# Breakout_v2.net
KiCad netlist of a schematic drawn in EAGLE
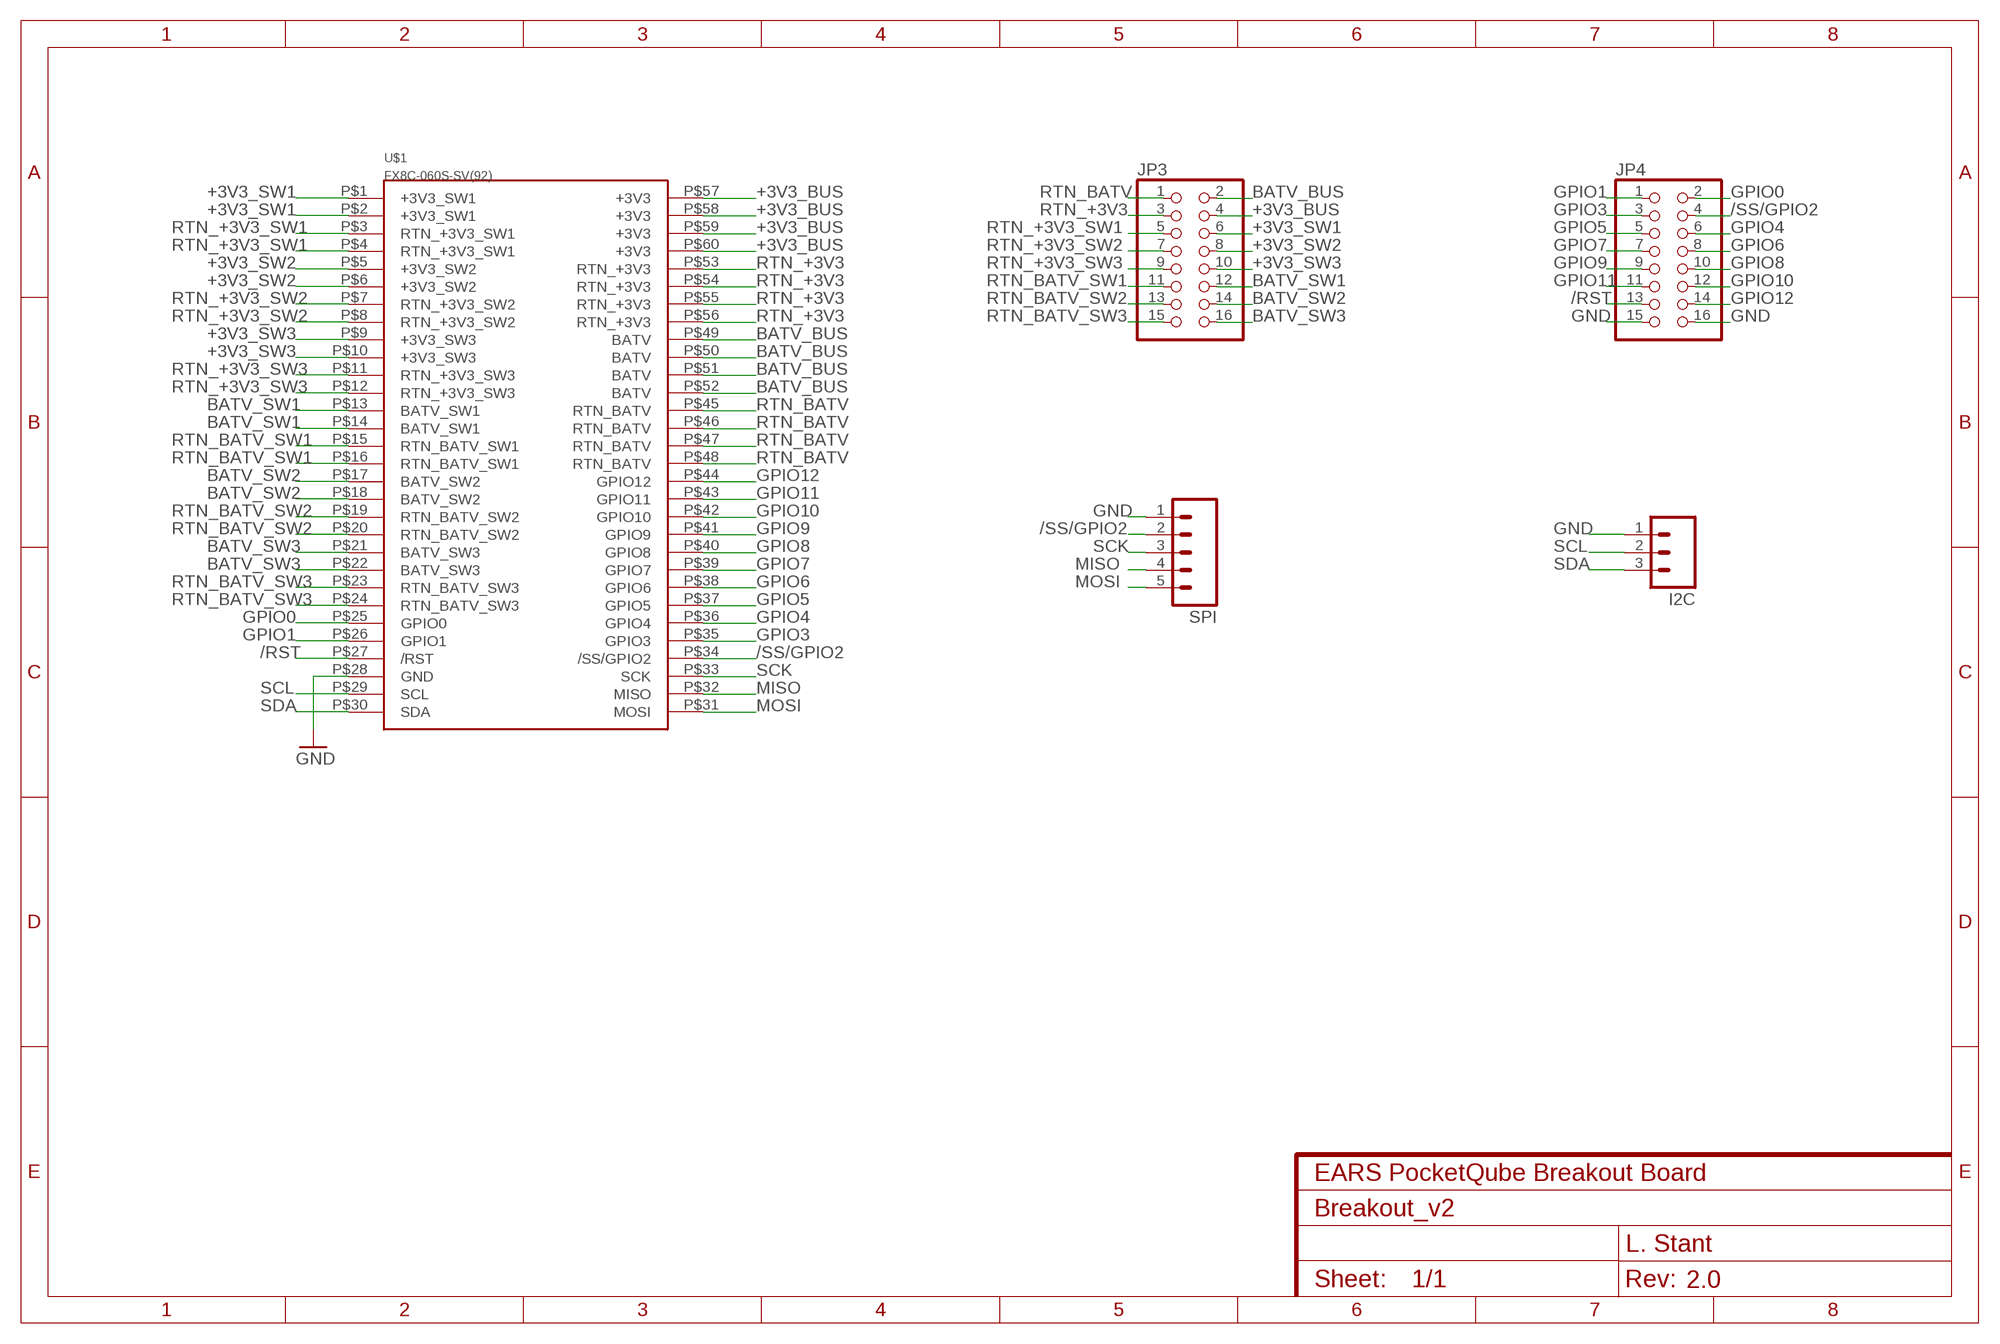
[diagram p0: schematic, sheet 1]

(export (version "E")
  (design (tool "Eeschema 10.0.6"))
  (components
    (comp (ref "I2C")
      (value "M03PTH")
      (footprint "eagle-import:1X03")
      (libsource (lib "eagle-import") (part "M03PTH"))
    )
    (comp (ref "JP3")
      (value "PINHD-2X8")
      (footprint "eagle-import:2X08")
      (libsource (lib "eagle-import") (part "PINHD-2X8"))
    )
    (comp (ref "JP4")
      (value "PINHD-2X8")
      (footprint "eagle-import:2X08")
      (libsource (lib "eagle-import") (part "PINHD-2X8"))
    )
    (comp (ref "SPI")
      (value "M05PTH")
      (footprint "eagle-import:1X05")
      (libsource (lib "eagle-import") (part "M05PTH"))
    )
    (comp (ref "U$1")
      (value "FX8C-060S-SV(92)")
      (footprint "eagle-import:FX8C-060S-SV(92)")
      (libsource (lib "eagle-import") (part "FX8C-060S-SV(92)"))
    )
  )
  (nets
    (net (code "1") (name "/+3V3_BUS") (class "Default")
      (node (ref "JP3") (pin "4") (pinfunction "4_4") (pintype "passive"))
      (node (ref "U$1") (pin "P$57") (pinfunction "+3V3_P$57") (pintype "power_in"))
      (node (ref "U$1") (pin "P$58") (pinfunction "+3V3_P$58") (pintype "power_in"))
      (node (ref "U$1") (pin "P$59") (pinfunction "+3V3_P$59") (pintype "power_in"))
      (node (ref "U$1") (pin "P$60") (pinfunction "+3V3_P$60") (pintype "power_in"))
    )
    (net (code "2") (name "/+3V3_SW1") (class "Default")
      (node (ref "JP3") (pin "6") (pinfunction "6_6") (pintype "passive"))
      (node (ref "U$1") (pin "P$1") (pinfunction "+3V3_SW1_P$1") (pintype "power_in"))
      (node (ref "U$1") (pin "P$2") (pinfunction "+3V3_SW1_P$2") (pintype "power_in"))
    )
    (net (code "3") (name "/+3V3_SW2") (class "Default")
      (node (ref "JP3") (pin "8") (pinfunction "8_8") (pintype "passive"))
      (node (ref "U$1") (pin "P$5") (pinfunction "+3V3_SW2_P$5") (pintype "power_in"))
      (node (ref "U$1") (pin "P$6") (pinfunction "+3V3_SW2_P$6") (pintype "power_in"))
    )
    (net (code "4") (name "/+3V3_SW3") (class "Default")
      (node (ref "JP3") (pin "10") (pinfunction "10_10") (pintype "passive"))
      (node (ref "U$1") (pin "P$10") (pinfunction "+3V3_SW3_P$10") (pintype "power_in"))
      (node (ref "U$1") (pin "P$9") (pinfunction "+3V3_SW3_P$9") (pintype "power_in"))
    )
    (net (code "5") (name "/BATV_BUS") (class "Default")
      (node (ref "JP3") (pin "2") (pinfunction "2_2") (pintype "passive"))
      (node (ref "U$1") (pin "P$49") (pinfunction "BATV_P$49") (pintype "power_in"))
      (node (ref "U$1") (pin "P$50") (pinfunction "BATV_P$50") (pintype "power_in"))
      (node (ref "U$1") (pin "P$51") (pinfunction "BATV_P$51") (pintype "power_in"))
      (node (ref "U$1") (pin "P$52") (pinfunction "BATV_P$52") (pintype "power_in"))
    )
    (net (code "6") (name "/BATV_SW1") (class "Default")
      (node (ref "JP3") (pin "12") (pinfunction "12_12") (pintype "passive"))
      (node (ref "U$1") (pin "P$13") (pinfunction "BATV_SW1_P$13") (pintype "power_in"))
      (node (ref "U$1") (pin "P$14") (pinfunction "BATV_SW1_P$14") (pintype "power_in"))
    )
    (net (code "7") (name "/BATV_SW2") (class "Default")
      (node (ref "JP3") (pin "14") (pinfunction "14_14") (pintype "passive"))
      (node (ref "U$1") (pin "P$17") (pinfunction "BATV_SW2_P$17") (pintype "power_in"))
      (node (ref "U$1") (pin "P$18") (pinfunction "BATV_SW2_P$18") (pintype "power_in"))
    )
    (net (code "8") (name "/BATV_SW3") (class "Default")
      (node (ref "JP3") (pin "16") (pinfunction "16_16") (pintype "passive"))
      (node (ref "U$1") (pin "P$21") (pinfunction "BATV_SW3_P$21") (pintype "power_in"))
      (node (ref "U$1") (pin "P$22") (pinfunction "BATV_SW3_P$22") (pintype "power_in"))
    )
    (net (code "9") (name "/GPIO0") (class "Default")
      (node (ref "JP4") (pin "2") (pinfunction "2_2") (pintype "passive"))
      (node (ref "U$1") (pin "P$25") (pinfunction "GPIO0_P$25") (pintype "bidirectional"))
    )
    (net (code "10") (name "/GPIO1") (class "Default")
      (node (ref "JP4") (pin "1") (pinfunction "1_1") (pintype "passive"))
      (node (ref "U$1") (pin "P$26") (pinfunction "GPIO1_P$26") (pintype "bidirectional"))
    )
    (net (code "11") (name "/GPIO3") (class "Default")
      (node (ref "JP4") (pin "3") (pinfunction "3_3") (pintype "passive"))
      (node (ref "U$1") (pin "P$35") (pinfunction "GPIO3_P$35") (pintype "bidirectional"))
    )
    (net (code "12") (name "/GPIO4") (class "Default")
      (node (ref "JP4") (pin "6") (pinfunction "6_6") (pintype "passive"))
      (node (ref "U$1") (pin "P$36") (pinfunction "GPIO4_P$36") (pintype "bidirectional"))
    )
    (net (code "13") (name "/GPIO5") (class "Default")
      (node (ref "JP4") (pin "5") (pinfunction "5_5") (pintype "passive"))
      (node (ref "U$1") (pin "P$37") (pinfunction "GPIO5_P$37") (pintype "bidirectional"))
    )
    (net (code "14") (name "/GPIO6") (class "Default")
      (node (ref "JP4") (pin "8") (pinfunction "8_8") (pintype "passive"))
      (node (ref "U$1") (pin "P$38") (pinfunction "GPIO6_P$38") (pintype "bidirectional"))
    )
    (net (code "15") (name "/GPIO7") (class "Default")
      (node (ref "JP4") (pin "7") (pinfunction "7_7") (pintype "passive"))
      (node (ref "U$1") (pin "P$39") (pinfunction "GPIO7_P$39") (pintype "bidirectional"))
    )
    (net (code "16") (name "/GPIO8") (class "Default")
      (node (ref "JP4") (pin "10") (pinfunction "10_10") (pintype "passive"))
      (node (ref "U$1") (pin "P$40") (pinfunction "GPIO8_P$40") (pintype "bidirectional"))
    )
    (net (code "17") (name "/GPIO9") (class "Default")
      (node (ref "JP4") (pin "9") (pinfunction "9_9") (pintype "passive"))
      (node (ref "U$1") (pin "P$41") (pinfunction "GPIO9_P$41") (pintype "bidirectional"))
    )
    (net (code "18") (name "/GPIO10") (class "Default")
      (node (ref "JP4") (pin "12") (pinfunction "12_12") (pintype "passive"))
      (node (ref "U$1") (pin "P$42") (pinfunction "GPIO10_P$42") (pintype "bidirectional"))
    )
    (net (code "19") (name "/GPIO11") (class "Default")
      (node (ref "JP4") (pin "11") (pinfunction "11_11") (pintype "passive"))
      (node (ref "U$1") (pin "P$43") (pinfunction "GPIO11_P$43") (pintype "bidirectional"))
    )
    (net (code "20") (name "/GPIO12") (class "Default")
      (node (ref "JP4") (pin "14") (pinfunction "14_14") (pintype "passive"))
      (node (ref "U$1") (pin "P$44") (pinfunction "GPIO12_P$44") (pintype "bidirectional"))
    )
    (net (code "21") (name "/MISO") (class "Default")
      (node (ref "SPI") (pin "4") (pinfunction "4_4") (pintype "passive"))
      (node (ref "U$1") (pin "P$32") (pinfunction "MISO_P$32") (pintype "bidirectional"))
    )
    (net (code "22") (name "/MOSI") (class "Default")
      (node (ref "SPI") (pin "5") (pinfunction "5_5") (pintype "passive"))
      (node (ref "U$1") (pin "P$31") (pinfunction "MOSI_P$31") (pintype "bidirectional"))
    )
    (net (code "23") (name "/RTN_+3V3") (class "Default")
      (node (ref "JP3") (pin "3") (pinfunction "3_3") (pintype "passive"))
      (node (ref "U$1") (pin "P$53") (pinfunction "RTN_+3V3_P$53") (pintype "power_in"))
      (node (ref "U$1") (pin "P$54") (pinfunction "RTN_+3V3_P$54") (pintype "power_in"))
      (node (ref "U$1") (pin "P$55") (pinfunction "RTN_+3V3_P$55") (pintype "power_in"))
      (node (ref "U$1") (pin "P$56") (pinfunction "RTN_+3V3_P$56") (pintype "power_in"))
    )
    (net (code "24") (name "/RTN_+3V3_SW1") (class "Default")
      (node (ref "JP3") (pin "5") (pinfunction "5_5") (pintype "passive"))
      (node (ref "U$1") (pin "P$3") (pinfunction "RTN_+3V3_SW1_P$3") (pintype "power_in"))
      (node (ref "U$1") (pin "P$4") (pinfunction "RTN_+3V3_SW1_P$4") (pintype "power_in"))
    )
    (net (code "25") (name "/RTN_+3V3_SW2") (class "Default")
      (node (ref "JP3") (pin "7") (pinfunction "7_7") (pintype "passive"))
      (node (ref "U$1") (pin "P$7") (pinfunction "RTN_+3V3_SW2_P$7") (pintype "power_in"))
      (node (ref "U$1") (pin "P$8") (pinfunction "RTN_+3V3_SW2_P$8") (pintype "power_in"))
    )
    (net (code "26") (name "/RTN_+3V3_SW3") (class "Default")
      (node (ref "JP3") (pin "9") (pinfunction "9_9") (pintype "passive"))
      (node (ref "U$1") (pin "P$11") (pinfunction "RTN_+3V3_SW3_P$11") (pintype "power_in"))
      (node (ref "U$1") (pin "P$12") (pinfunction "RTN_+3V3_SW3_P$12") (pintype "power_in"))
    )
    (net (code "27") (name "/RTN_BATV") (class "Default")
      (node (ref "JP3") (pin "1") (pinfunction "1_1") (pintype "passive"))
      (node (ref "U$1") (pin "P$45") (pinfunction "RTN_BATV_P$45") (pintype "power_in"))
      (node (ref "U$1") (pin "P$46") (pinfunction "RTN_BATV_P$46") (pintype "power_in"))
      (node (ref "U$1") (pin "P$47") (pinfunction "RTN_BATV_P$47") (pintype "power_in"))
      (node (ref "U$1") (pin "P$48") (pinfunction "RTN_BATV_P$48") (pintype "power_in"))
    )
    (net (code "28") (name "/RTN_BATV_SW1") (class "Default")
      (node (ref "JP3") (pin "11") (pinfunction "11_11") (pintype "passive"))
      (node (ref "U$1") (pin "P$15") (pinfunction "RTN_BATV_SW1_P$15") (pintype "power_in"))
      (node (ref "U$1") (pin "P$16") (pinfunction "RTN_BATV_SW1_P$16") (pintype "power_in"))
    )
    (net (code "29") (name "/RTN_BATV_SW2") (class "Default")
      (node (ref "JP3") (pin "13") (pinfunction "13_13") (pintype "passive"))
      (node (ref "U$1") (pin "P$19") (pinfunction "RTN_BATV_SW2_P$19") (pintype "power_in"))
      (node (ref "U$1") (pin "P$20") (pinfunction "RTN_BATV_SW2_P$20") (pintype "power_in"))
    )
    (net (code "30") (name "/RTN_BATV_SW3") (class "Default")
      (node (ref "JP3") (pin "15") (pinfunction "15_15") (pintype "passive"))
      (node (ref "U$1") (pin "P$23") (pinfunction "RTN_BATV_SW3_P$23") (pintype "power_in"))
      (node (ref "U$1") (pin "P$24") (pinfunction "RTN_BATV_SW3_P$24") (pintype "power_in"))
    )
    (net (code "31") (name "/SCK") (class "Default")
      (node (ref "SPI") (pin "3") (pinfunction "3_3") (pintype "passive"))
      (node (ref "U$1") (pin "P$33") (pinfunction "SCK_P$33") (pintype "bidirectional"))
    )
    (net (code "32") (name "/SCL") (class "Default")
      (node (ref "I2C") (pin "2") (pinfunction "2_2") (pintype "passive"))
      (node (ref "U$1") (pin "P$29") (pinfunction "SCL_P$29") (pintype "bidirectional"))
    )
    (net (code "33") (name "/SDA") (class "Default")
      (node (ref "I2C") (pin "3") (pinfunction "3_3") (pintype "passive"))
      (node (ref "U$1") (pin "P$30") (pinfunction "SDA_P$30") (pintype "bidirectional"))
    )
    (net (code "34") (name "/{slash}RST") (class "Default")
      (node (ref "JP4") (pin "13") (pinfunction "13_13") (pintype "passive"))
      (node (ref "U$1") (pin "P$27") (pinfunction "/RST_P$27") (pintype "bidirectional"))
    )
    (net (code "35") (name "/{slash}SS{slash}GPIO2") (class "Default")
      (node (ref "JP4") (pin "4") (pinfunction "4_4") (pintype "passive"))
      (node (ref "SPI") (pin "2") (pinfunction "2_2") (pintype "passive"))
      (node (ref "U$1") (pin "P$34") (pinfunction "/SS/GPIO2_P$34") (pintype "bidirectional"))
    )
    (net (code "36") (name "GND") (class "Default")
      (node (ref "I2C") (pin "1") (pinfunction "1_1") (pintype "passive"))
      (node (ref "JP4") (pin "15") (pinfunction "15_15") (pintype "passive"))
      (node (ref "JP4") (pin "16") (pinfunction "16_16") (pintype "passive"))
      (node (ref "SPI") (pin "1") (pinfunction "1_1") (pintype "passive"))
      (node (ref "U$1") (pin "P$28") (pinfunction "GND_P$28") (pintype "bidirectional"))
    )
  )
)
